# SCH_GSME_voltmeter_Arduino_ESP8266_TP405.net
KiCad netlist of a schematic drawn in EasyEDA
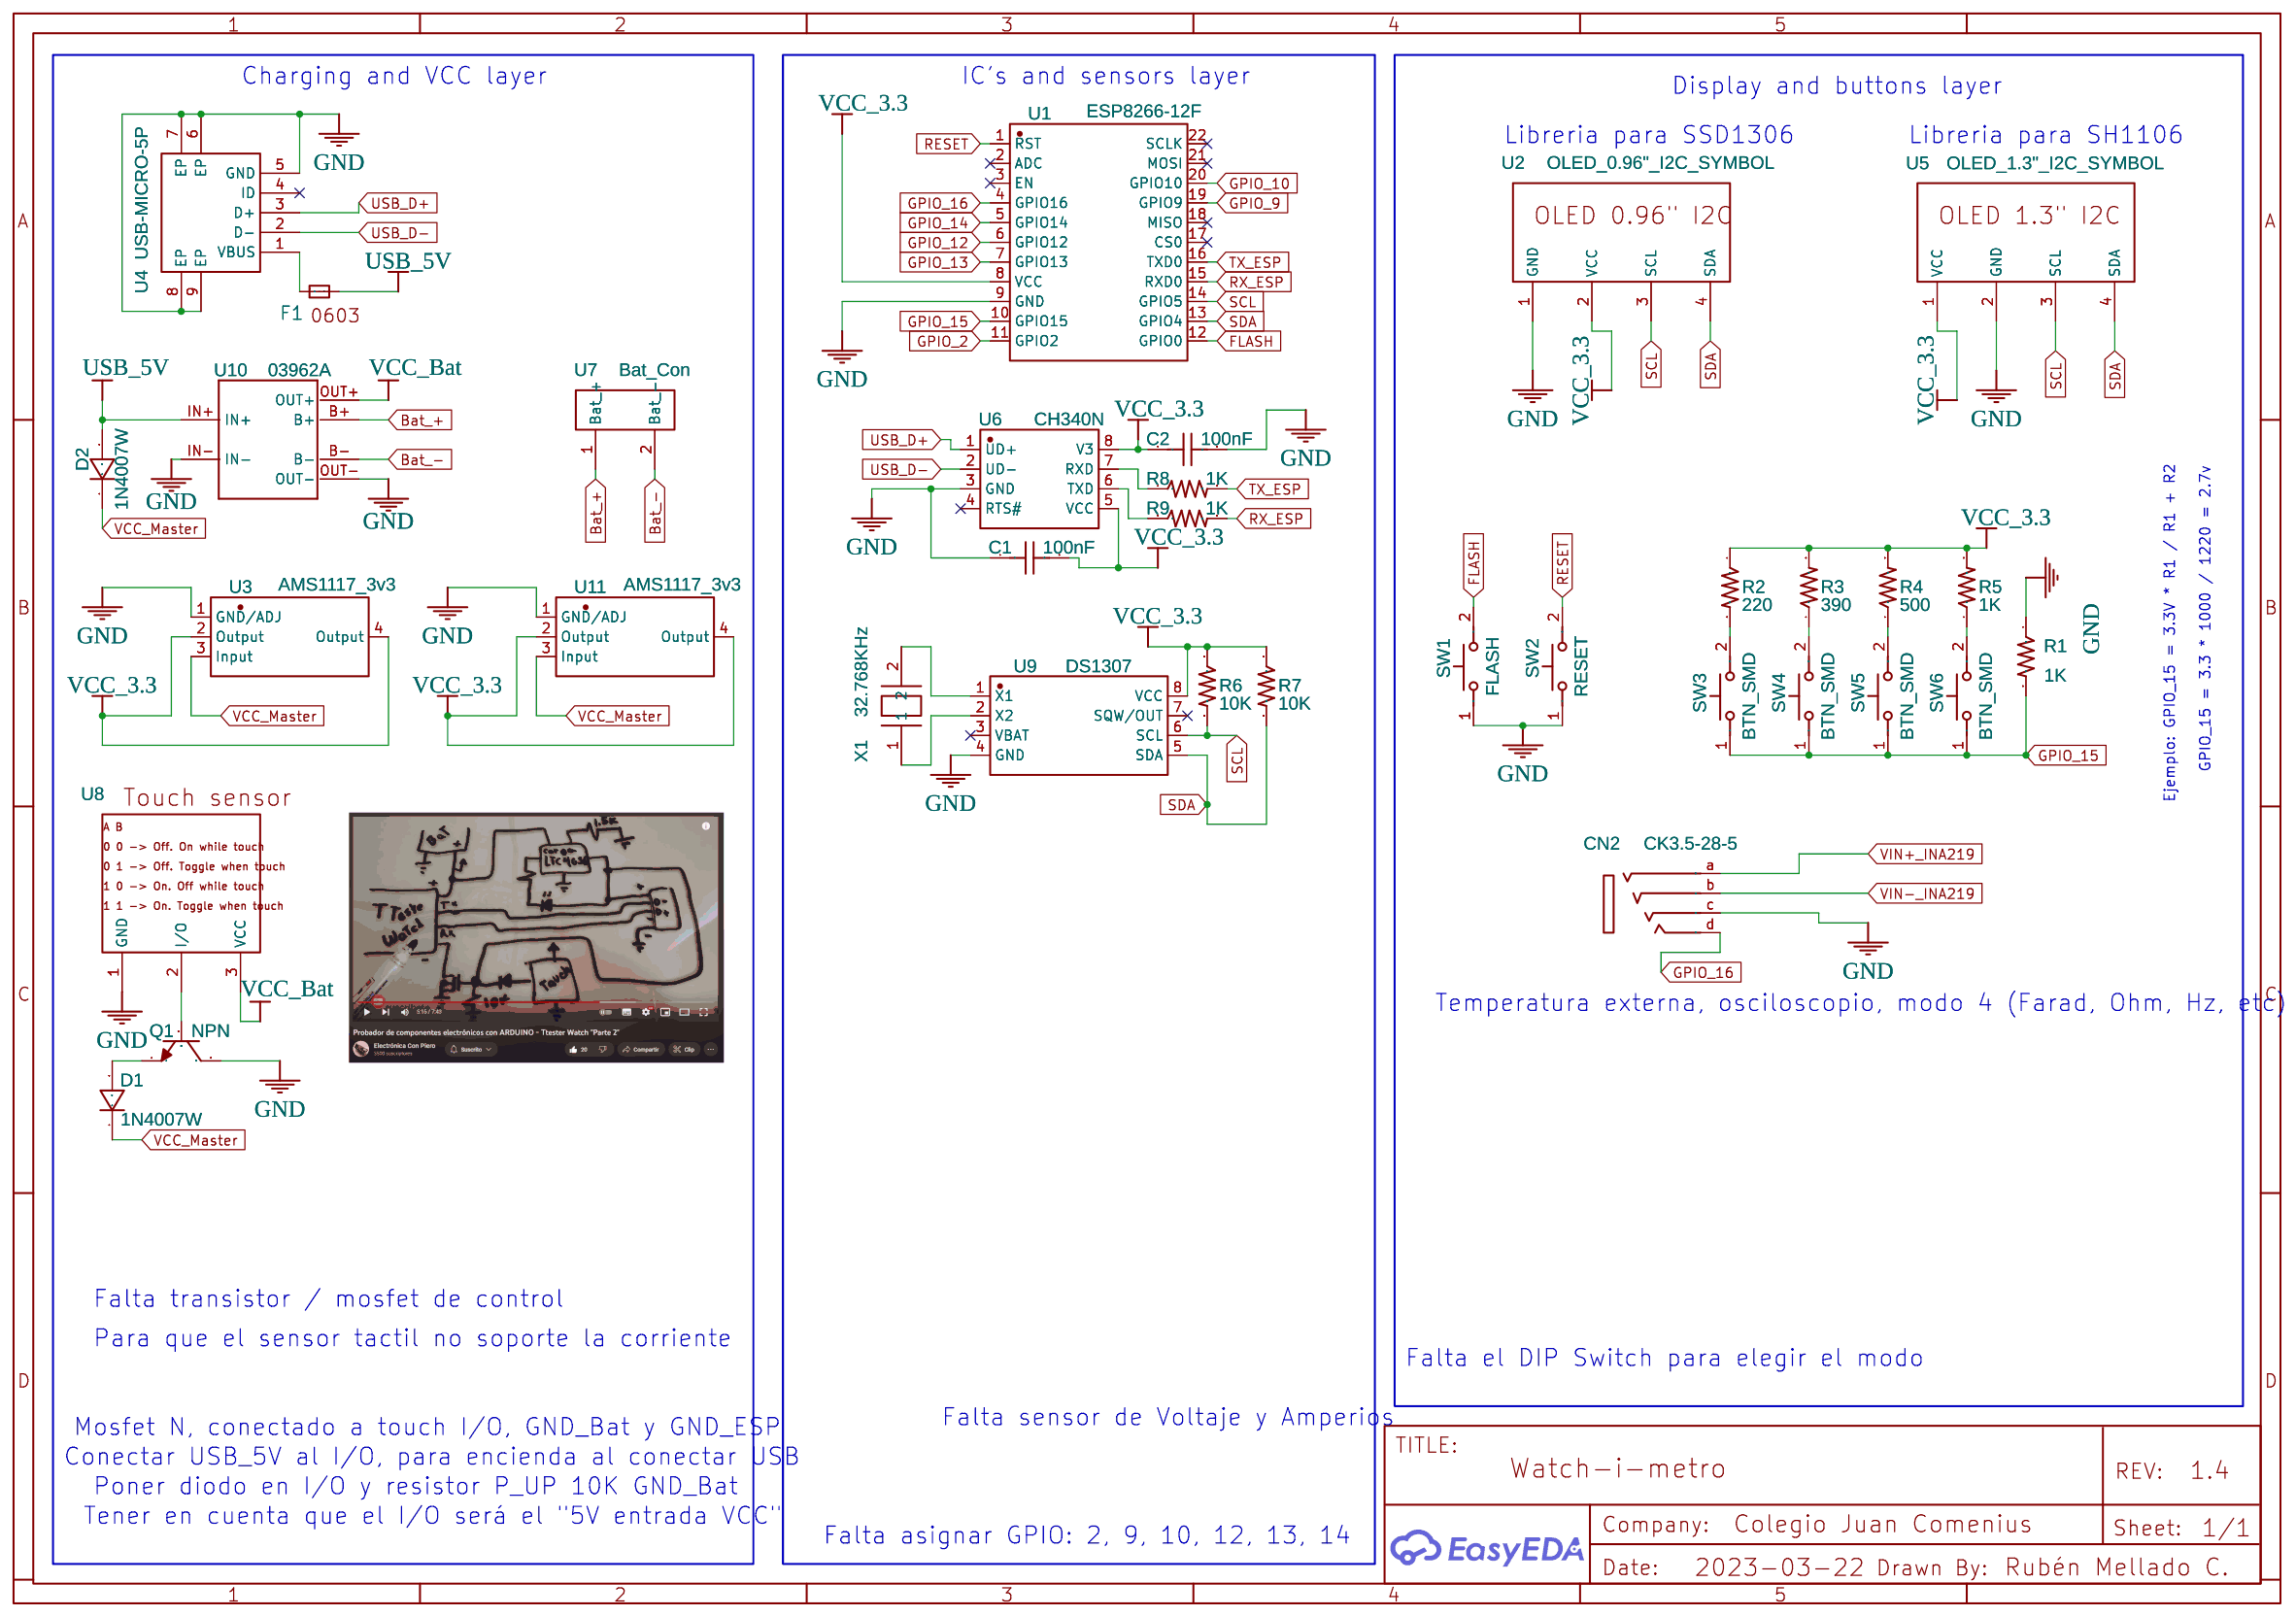
[diagram p0: schematic sheet]

(export (version "E")
  (design (tool "Eeschema 10.0.6"))
  (components
    (comp (ref "C1") (value "100nF") (libsource (lib "") (part "C_0603_US")))
    (comp (ref "C2") (value "100nF") (libsource (lib "") (part "C_0603_US")))
    (comp (ref "CN2")
      (value "CK3.5-28-5")
      (fields (field (name "BOM_Supplier Part") "C718048"))
      (libsource (lib "") (part "CK3.5-28-5"))
    )
    (comp (ref "D1")
      (value "1N4007W")
      (fields (field (name "BOM_Supplier Part") "C328592"))
      (libsource (lib "") (part "1N4007W"))
    )
    (comp (ref "D2")
      (value "1N4007W")
      (fields (field (name "BOM_Supplier Part") "C328592"))
      (libsource (lib "") (part "1N4007W"))
    )
    (comp (ref "F1")
      (value "Fuse")
      (fields (field (name "BOM_Manufacturer Part") "0603") (field (name "BOM_Supplier Part") "C9900014602"))
      (libsource (lib "") (part "0603_FUSE_SYMBOL"))
    )
    (comp (ref "Q1")
      (value "NPN")
      (fields
        (field (name "BOM_Manufacturer Part") "2n3904S-RTK/PS")
        (field (name "BOM_Supplier Part") "C18536")
      )
      (libsource (lib "") (part "2N3904(SOT-23)"))
    )
    (comp (ref "R1") (value "1K") (libsource (lib "") (part "RESISTOR0603")))
    (comp (ref "R2") (value "220") (libsource (lib "") (part "RESISTOR0603")))
    (comp (ref "R3") (value "390") (libsource (lib "") (part "RESISTOR0603_2")))
    (comp (ref "R4") (value "500") (libsource (lib "") (part "RESISTOR0603_2")))
    (comp (ref "R5") (value "1K") (libsource (lib "") (part "RESISTOR0603_2")))
    (comp (ref "R6") (value "10K") (libsource (lib "") (part "RESISTOR0603")))
    (comp (ref "R7") (value "10K") (libsource (lib "") (part "RESISTOR0603")))
    (comp (ref "R8") (value "1K") (libsource (lib "") (part "RESISTOR0603_1")))
    (comp (ref "R9") (value "1K") (libsource (lib "") (part "RESISTOR0603_1")))
    (comp (ref "SW1")
      (value "FLASH")
      (fields
        (field (name "BOM_Manufacturer Part") "BUTTON2")
        (field (name "BOM_Supplier Part") "C9900005988")
      )
      (libsource (lib "") (part "BUTTON2"))
    )
    (comp (ref "SW2")
      (value "RESET")
      (fields
        (field (name "BOM_Manufacturer Part") "BUTTON2")
        (field (name "BOM_Supplier Part") "C9900005988")
      )
      (libsource (lib "") (part "BUTTON2"))
    )
    (comp (ref "SW3")
      (value "BTN_SMD")
      (fields
        (field (name "BOM_Manufacturer Part") "BUTTON2")
        (field (name "BOM_Supplier Part") "C9900005988")
      )
      (libsource (lib "") (part "BUTTON2"))
    )
    (comp (ref "SW4")
      (value "BTN_SMD")
      (fields
        (field (name "BOM_Manufacturer Part") "BUTTON2")
        (field (name "BOM_Supplier Part") "C9900005988")
      )
      (libsource (lib "") (part "BUTTON2"))
    )
    (comp (ref "SW5")
      (value "BTN_SMD")
      (fields
        (field (name "BOM_Manufacturer Part") "BUTTON2")
        (field (name "BOM_Supplier Part") "C9900005988")
      )
      (libsource (lib "") (part "BUTTON2"))
    )
    (comp (ref "SW6")
      (value "BTN_SMD")
      (fields
        (field (name "BOM_Manufacturer Part") "BUTTON2")
        (field (name "BOM_Supplier Part") "C9900005988")
      )
      (libsource (lib "") (part "BUTTON2"))
    )
    (comp (ref "U1")
      (value "ESP8266-12F")
      (fields
        (field (name "BOM_Manufacturer Part") "ESP-12F(ESP8266MOD)")
        (field (name "BOM_Supplier Part") "C82891")
      )
      (libsource (lib "") (part "ESP-12F(ESP8266MOD)"))
    )
    (comp (ref "U2")
      (value "OLED_0.96\"_I2C_SYMBOL")
      (libsource (lib "") (part "OLED_0.96{dblquote}_I2C_SYMBOL"))
    )
    (comp (ref "U3")
      (value "AMS1117_3v3")
      (fields
        (field (name "BOM_Manufacturer Part") "AMS1117-3.3S")
        (field (name "BOM_Supplier Part") "C2842296")
      )
      (libsource (lib "") (part "AMS1117-3.3S"))
    )
    (comp (ref "U4")
      (value "USB-MICRO-5P")
      (fields
        (field (name "BOM_Manufacturer Part") "USB-Micro-5P")
        (field (name "BOM_Supplier Part") "C9900014288")
      )
      (libsource (lib "") (part "USB-MICRO-5P"))
    )
    (comp (ref "U5")
      (value "OLED_1.3\"_I2C_SYMBOL")
      (libsource (lib "") (part "OLED_1.3{dblquote}_I2C_SYMBOL"))
    )
    (comp (ref "U6")
      (value "CH340N")
      (fields (field (name "BOM_Supplier Part") "C506813"))
      (libsource (lib "") (part "CH340N"))
    )
    (comp (ref "U7") (value "Bat_Con") (libsource (lib "") (part "Connector_Battery_2_Wires_2p")))
    (comp (ref "U8") (value "Touch_Sensor") (libsource (lib "") (part "Touch_Sensor_3p_A_B_SYMBOL")))
    (comp (ref "U9")
      (value "DS1307")
      (fields
        (field (name "BOM_Manufacturer Part") "DS1307M/TR")
        (field (name "BOM_Supplier Part") "C356706")
      )
      (libsource (lib "") (part "DS1307M/TR"))
    )
    (comp (ref "U10") (value "03962A") (libsource (lib "") (part "03962A")))
    (comp (ref "U11")
      (value "AMS1117_3v3")
      (fields
        (field (name "BOM_Manufacturer Part") "AMS1117-3.3S")
        (field (name "BOM_Supplier Part") "C2842296")
      )
      (libsource (lib "") (part "AMS1117-3.3S"))
    )
    (comp (ref "X1") (value "32.768KHz") (libsource (lib "") (part "Quartz_X_2p_Symbol")))
  )
  (nets
    (net (code "1") (name "Bat_+") (class "Default")
      (node (ref "U10") (pin "B+") (pinfunction "B+_B+") (pintype "bidirectional"))
      (node (ref "U7") (pin "1") (pinfunction "Bat_+_1") (pintype "unspecified"))
    )
    (net (code "2") (name "Bat_-") (class "Default")
      (node (ref "U10") (pin "B-") (pinfunction "B-_B-") (pintype "bidirectional"))
      (node (ref "U7") (pin "2") (pinfunction "Bat_-_2") (pintype "unspecified"))
    )
    (net (code "3") (name "FLASH") (class "Default")
      (node (ref "SW1") (pin "2") (pinfunction "2_2") (pintype "unspecified"))
      (node (ref "U1") (pin "12") (pinfunction "GPIO0_12") (pintype "unspecified"))
    )
    (net (code "4") (name "GND") (class "Default")
      (node (ref "C1") (pin "1") (pinfunction "1_1") (pintype "unspecified"))
      (node (ref "C2") (pin "2") (pinfunction "2_2") (pintype "unspecified"))
      (node (ref "CN2") (pin "c") (pinfunction "c_c") (pintype "unspecified"))
      (node (ref "Q1") (pin "2") (pinfunction "C_2") (pintype "input"))
      (node (ref "R1") (pin "1") (pinfunction "1_1") (pintype "unspecified"))
      (node (ref "SW1") (pin "1") (pinfunction "1_1") (pintype "unspecified"))
      (node (ref "SW2") (pin "1") (pinfunction "1_1") (pintype "unspecified"))
      (node (ref "U1") (pin "9") (pinfunction "GND_9") (pintype "unspecified"))
      (node (ref "U10") (pin "IN-") (pinfunction "IN-_IN-") (pintype "bidirectional"))
      (node (ref "U10") (pin "OUT-") (pinfunction "OUT-_OUT-") (pintype "bidirectional"))
      (node (ref "U11") (pin "1") (pinfunction "GND/ADJ_1") (pintype "unspecified"))
      (node (ref "U2") (pin "1") (pinfunction "GND_1") (pintype "unspecified"))
      (node (ref "U3") (pin "1") (pinfunction "GND/ADJ_1") (pintype "unspecified"))
      (node (ref "U4") (pin "5") (pinfunction "GND_5") (pintype "unspecified"))
      (node (ref "U4") (pin "6") (pinfunction "EP_6") (pintype "unspecified"))
      (node (ref "U4") (pin "7") (pinfunction "EP_7") (pintype "unspecified"))
      (node (ref "U4") (pin "8") (pinfunction "EP_8") (pintype "unspecified"))
      (node (ref "U4") (pin "9") (pinfunction "EP_9") (pintype "unspecified"))
      (node (ref "U5") (pin "2") (pinfunction "GND_2") (pintype "unspecified"))
      (node (ref "U6") (pin "3") (pinfunction "GND_3") (pintype "unspecified"))
      (node (ref "U8") (pin "1") (pinfunction "GND_1") (pintype "unspecified"))
      (node (ref "U9") (pin "4") (pinfunction "GND_4") (pintype "unspecified"))
    )
    (net (code "5") (name "GPIO_2") (class "Default")
      (node (ref "U1") (pin "11") (pinfunction "GPIO2_11") (pintype "unspecified"))
    )
    (net (code "6") (name "GPIO_9") (class "Default")
      (node (ref "U1") (pin "19") (pinfunction "GPIO9_19") (pintype "unspecified"))
    )
    (net (code "7") (name "GPIO_10") (class "Default")
      (node (ref "U1") (pin "20") (pinfunction "GPIO10_20") (pintype "unspecified"))
    )
    (net (code "8") (name "GPIO_12") (class "Default")
      (node (ref "U1") (pin "6") (pinfunction "GPIO12_6") (pintype "unspecified"))
    )
    (net (code "9") (name "GPIO_13") (class "Default")
      (node (ref "U1") (pin "7") (pinfunction "GPIO13_7") (pintype "unspecified"))
    )
    (net (code "10") (name "GPIO_14") (class "Default")
      (node (ref "U1") (pin "5") (pinfunction "GPIO14_5") (pintype "unspecified"))
    )
    (net (code "11") (name "GPIO_15") (class "Default")
      (node (ref "R1") (pin "2") (pinfunction "2_2") (pintype "unspecified"))
      (node (ref "SW3") (pin "1") (pinfunction "1_1") (pintype "unspecified"))
      (node (ref "SW4") (pin "1") (pinfunction "1_1") (pintype "unspecified"))
      (node (ref "SW5") (pin "1") (pinfunction "1_1") (pintype "unspecified"))
      (node (ref "SW6") (pin "1") (pinfunction "1_1") (pintype "unspecified"))
      (node (ref "U1") (pin "10") (pinfunction "GPIO15_10") (pintype "unspecified"))
    )
    (net (code "12") (name "GPIO_16") (class "Default")
      (node (ref "CN2") (pin "d") (pinfunction "d_d") (pintype "unspecified"))
      (node (ref "U1") (pin "4") (pinfunction "GPIO16_4") (pintype "unspecified"))
    )
    (net (code "13") (name "Net-(F1-K)") (class "Default")
      (node (ref "F1") (pin "1") (pinfunction "K_1") (pintype "unspecified"))
      (node (ref "U4") (pin "1") (pinfunction "VBUS_1") (pintype "unspecified"))
    )
    (net (code "14") (name "Net-(Q1-B)") (class "Default")
      (node (ref "Q1") (pin "3") (pinfunction "B_3") (pintype "input"))
      (node (ref "U8") (pin "2") (pinfunction "I/O_2") (pintype "unspecified"))
    )
    (net (code "15") (name "Net-(Q1-E)") (class "Default")
      (node (ref "D1") (pin "2") (pinfunction "2_2") (pintype "unspecified"))
      (node (ref "Q1") (pin "1") (pinfunction "E_1") (pintype "input"))
    )
    (net (code "16") (name "Net-(R2-Pad2)") (class "Default")
      (node (ref "R2") (pin "2") (pinfunction "2_2") (pintype "unspecified"))
      (node (ref "SW3") (pin "2") (pinfunction "2_2") (pintype "unspecified"))
    )
    (net (code "17") (name "Net-(R3-Pad1)") (class "Default")
      (node (ref "R3") (pin "1") (pinfunction "1_1") (pintype "unspecified"))
      (node (ref "SW4") (pin "2") (pinfunction "2_2") (pintype "unspecified"))
    )
    (net (code "18") (name "Net-(R4-Pad1)") (class "Default")
      (node (ref "R4") (pin "1") (pinfunction "1_1") (pintype "unspecified"))
      (node (ref "SW5") (pin "2") (pinfunction "2_2") (pintype "unspecified"))
    )
    (net (code "19") (name "Net-(R5-Pad1)") (class "Default")
      (node (ref "R5") (pin "1") (pinfunction "1_1") (pintype "unspecified"))
      (node (ref "SW6") (pin "2") (pinfunction "2_2") (pintype "unspecified"))
    )
    (net (code "20") (name "Net-(U6-RXD)") (class "Default")
      (node (ref "R8") (pin "1") (pinfunction "1_1") (pintype "unspecified"))
      (node (ref "U6") (pin "7") (pinfunction "RXD_7") (pintype "unspecified"))
    )
    (net (code "21") (name "Net-(U6-TXD)") (class "Default")
      (node (ref "R9") (pin "1") (pinfunction "1_1") (pintype "unspecified"))
      (node (ref "U6") (pin "6") (pinfunction "TXD_6") (pintype "unspecified"))
    )
    (net (code "22") (name "Net-(U9-X1)") (class "Default")
      (node (ref "U9") (pin "1") (pinfunction "X1_1") (pintype "unspecified"))
      (node (ref "X1") (pin "2") (pinfunction "2_2") (pintype "unspecified"))
    )
    (net (code "23") (name "Net-(U9-X2)") (class "Default")
      (node (ref "U9") (pin "2") (pinfunction "X2_2") (pintype "unspecified"))
      (node (ref "X1") (pin "1") (pinfunction "1_1") (pintype "unspecified"))
    )
    (net (code "24") (name "RESET") (class "Default")
      (node (ref "SW2") (pin "2") (pinfunction "2_2") (pintype "unspecified"))
      (node (ref "U1") (pin "1") (pinfunction "RST_1") (pintype "unspecified"))
    )
    (net (code "25") (name "RX_ESP") (class "Default")
      (node (ref "R9") (pin "2") (pinfunction "2_2") (pintype "unspecified"))
      (node (ref "U1") (pin "15") (pinfunction "RXD0_15") (pintype "unspecified"))
    )
    (net (code "26") (name "SCL") (class "Default")
      (node (ref "R6") (pin "2") (pinfunction "2_2") (pintype "unspecified"))
      (node (ref "U1") (pin "14") (pinfunction "GPIO5_14") (pintype "unspecified"))
      (node (ref "U2") (pin "3") (pinfunction "SCL_3") (pintype "unspecified"))
      (node (ref "U5") (pin "3") (pinfunction "SCL_3") (pintype "unspecified"))
      (node (ref "U9") (pin "6") (pinfunction "SCL_6") (pintype "unspecified"))
    )
    (net (code "27") (name "SDA") (class "Default")
      (node (ref "R7") (pin "2") (pinfunction "2_2") (pintype "unspecified"))
      (node (ref "U1") (pin "13") (pinfunction "GPIO4_13") (pintype "unspecified"))
      (node (ref "U2") (pin "4") (pinfunction "SDA_4") (pintype "unspecified"))
      (node (ref "U5") (pin "4") (pinfunction "SDA_4") (pintype "unspecified"))
      (node (ref "U9") (pin "5") (pinfunction "SDA_5") (pintype "unspecified"))
    )
    (net (code "28") (name "TX_ESP") (class "Default")
      (node (ref "R8") (pin "2") (pinfunction "2_2") (pintype "unspecified"))
      (node (ref "U1") (pin "16") (pinfunction "TXD0_16") (pintype "unspecified"))
    )
    (net (code "29") (name "USB_5V") (class "Default")
      (node (ref "D2") (pin "2") (pinfunction "2_2") (pintype "unspecified"))
      (node (ref "F1") (pin "2") (pinfunction "A_2") (pintype "unspecified"))
      (node (ref "U10") (pin "IN+") (pinfunction "IN+_IN+") (pintype "bidirectional"))
    )
    (net (code "30") (name "USB_D+") (class "Default")
      (node (ref "U4") (pin "3") (pinfunction "D+_3") (pintype "unspecified"))
      (node (ref "U6") (pin "1") (pinfunction "UD+_1") (pintype "unspecified"))
    )
    (net (code "31") (name "USB_D-") (class "Default")
      (node (ref "U4") (pin "2") (pinfunction "D-_2") (pintype "unspecified"))
      (node (ref "U6") (pin "2") (pinfunction "UD-_2") (pintype "unspecified"))
    )
    (net (code "32") (name "VCC_3.3") (class "Default")
      (node (ref "C1") (pin "2") (pinfunction "2_2") (pintype "unspecified"))
      (node (ref "C2") (pin "1") (pinfunction "1_1") (pintype "unspecified"))
      (node (ref "R2") (pin "1") (pinfunction "1_1") (pintype "unspecified"))
      (node (ref "R3") (pin "2") (pinfunction "2_2") (pintype "unspecified"))
      (node (ref "R4") (pin "2") (pinfunction "2_2") (pintype "unspecified"))
      (node (ref "R5") (pin "2") (pinfunction "2_2") (pintype "unspecified"))
      (node (ref "R6") (pin "1") (pinfunction "1_1") (pintype "unspecified"))
      (node (ref "R7") (pin "1") (pinfunction "1_1") (pintype "unspecified"))
      (node (ref "U1") (pin "8") (pinfunction "VCC_8") (pintype "unspecified"))
      (node (ref "U11") (pin "2") (pinfunction "Output_2") (pintype "unspecified"))
      (node (ref "U11") (pin "4") (pinfunction "Output_4") (pintype "unspecified"))
      (node (ref "U2") (pin "2") (pinfunction "VCC_2") (pintype "unspecified"))
      (node (ref "U3") (pin "2") (pinfunction "Output_2") (pintype "unspecified"))
      (node (ref "U3") (pin "4") (pinfunction "Output_4") (pintype "unspecified"))
      (node (ref "U5") (pin "1") (pinfunction "VCC_1") (pintype "unspecified"))
      (node (ref "U6") (pin "5") (pinfunction "VCC_5") (pintype "unspecified"))
      (node (ref "U6") (pin "8") (pinfunction "V3_8") (pintype "unspecified"))
      (node (ref "U9") (pin "8") (pinfunction "VCC_8") (pintype "unspecified"))
    )
    (net (code "33") (name "VCC_Bat") (class "Default")
      (node (ref "U10") (pin "OUT+") (pinfunction "OUT+_OUT+") (pintype "bidirectional"))
      (node (ref "U8") (pin "3") (pinfunction "VCC_3") (pintype "unspecified"))
    )
    (net (code "34") (name "VCC_Master") (class "Default")
      (node (ref "D1") (pin "1") (pinfunction "1_1") (pintype "unspecified"))
      (node (ref "D2") (pin "1") (pinfunction "1_1") (pintype "unspecified"))
      (node (ref "U11") (pin "3") (pinfunction "Input_3") (pintype "unspecified"))
      (node (ref "U3") (pin "3") (pinfunction "Input_3") (pintype "unspecified"))
    )
    (net (code "35") (name "VIN+_INA219") (class "Default")
      (node (ref "CN2") (pin "a") (pinfunction "a_a") (pintype "unspecified"))
    )
    (net (code "36") (name "VIN-_INA219") (class "Default")
      (node (ref "CN2") (pin "b") (pinfunction "b_b") (pintype "unspecified"))
    )
    (net (code "37") (name "unconnected-(U1-ADC-Pad2)") (class "Default")
      (node (ref "U1") (pin "2") (pinfunction "ADC_2") (pintype "unspecified+no_connect"))
    )
    (net (code "38") (name "unconnected-(U1-CS0-Pad17)") (class "Default")
      (node (ref "U1") (pin "17") (pinfunction "CS0_17") (pintype "unspecified+no_connect"))
    )
    (net (code "39") (name "unconnected-(U1-EN-Pad3)") (class "Default")
      (node (ref "U1") (pin "3") (pinfunction "EN_3") (pintype "unspecified+no_connect"))
    )
    (net (code "40") (name "unconnected-(U1-MISO-Pad18)") (class "Default")
      (node (ref "U1") (pin "18") (pinfunction "MISO_18") (pintype "unspecified+no_connect"))
    )
    (net (code "41") (name "unconnected-(U1-MOSI-Pad21)") (class "Default")
      (node (ref "U1") (pin "21") (pinfunction "MOSI_21") (pintype "unspecified+no_connect"))
    )
    (net (code "42") (name "unconnected-(U1-SCLK-Pad22)") (class "Default")
      (node (ref "U1") (pin "22") (pinfunction "SCLK_22") (pintype "unspecified+no_connect"))
    )
    (net (code "43") (name "unconnected-(U4-ID-Pad4)") (class "Default")
      (node (ref "U4") (pin "4") (pinfunction "ID_4") (pintype "unspecified+no_connect"))
    )
    (net (code "44") (name "unconnected-(U6-RTS#-Pad4)") (class "Default")
      (node (ref "U6") (pin "4") (pinfunction "RTS#_4") (pintype "unspecified+no_connect"))
    )
    (net (code "45") (name "unconnected-(U9-SQW{slash}OUT-Pad7)") (class "Default")
      (node (ref "U9") (pin "7") (pinfunction "SQW/OUT_7") (pintype "unspecified+no_connect"))
    )
    (net (code "46") (name "unconnected-(U9-VBAT-Pad3)") (class "Default")
      (node (ref "U9") (pin "3") (pinfunction "VBAT_3") (pintype "unspecified+no_connect"))
    )
  )
)
